# hall_sensor_break_out.net
KiCad netlist of a schematic drawn in EAGLE
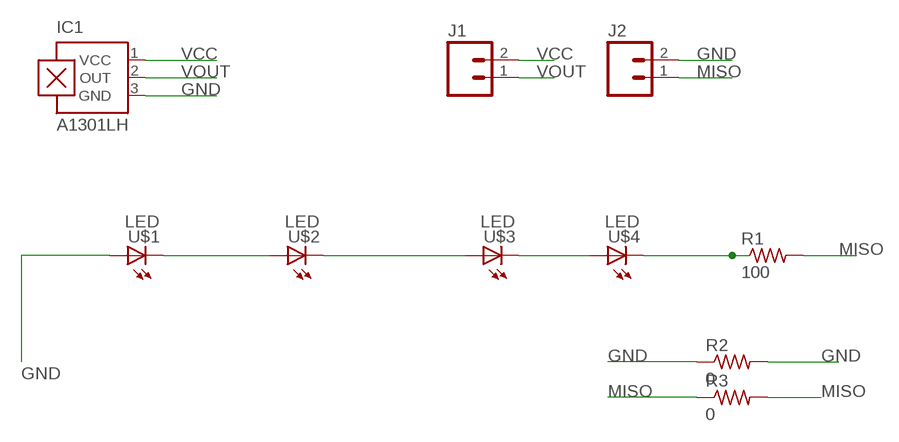
[diagram p0: schematic, sheet 1]

(export (version "E")
  (design (tool "Eeschema 10.0.6"))
  (components
    (comp (ref "IC1")
      (value "A1301LH")
      (footprint "eagle-import:SOT23-W")
      (fields (field (name "MF") "ALLEGRO MICROSYSTEMS, INC.") (field (name "MPN") "A1301ELHLT-T"))
      (libsource (lib "eagle-import") (part "A13?LH01"))
    )
    (comp (ref "J1")
      (value "M02POLAR_LOCK")
      (footprint "eagle-import:MOLEX-1X2_LOCK")
      (libsource (lib "eagle-import") (part "M02POLAR_LOCK"))
    )
    (comp (ref "J2")
      (value "M02POLAR_LOCK")
      (footprint "eagle-import:MOLEX-1X2_LOCK")
      (libsource (lib "eagle-import") (part "M02POLAR_LOCK"))
    )
    (comp (ref "R1")
      (value "100")
      (footprint "eagle-import:R1206FAB")
      (libsource (lib "eagle-import") (part "RES-US1206FAB"))
    )
    (comp (ref "R2")
      (value "0")
      (footprint "eagle-import:R1206FAB")
      (libsource (lib "eagle-import") (part "RES-US1206FAB"))
    )
    (comp (ref "R3")
      (value "0")
      (footprint "eagle-import:R1206FAB")
      (libsource (lib "eagle-import") (part "RES-US1206FAB"))
    )
    (comp (ref "U$1")
      (value "LED")
      (footprint "eagle-import:LED1206")
      (libsource (lib "eagle-import") (part "LED"))
    )
    (comp (ref "U$2")
      (value "LED")
      (footprint "eagle-import:LED1206")
      (libsource (lib "eagle-import") (part "LED"))
    )
    (comp (ref "U$3")
      (value "LED")
      (footprint "eagle-import:LED1206")
      (libsource (lib "eagle-import") (part "LED"))
    )
    (comp (ref "U$4")
      (value "LED")
      (footprint "eagle-import:LED1206")
      (libsource (lib "eagle-import") (part "LED"))
    )
  )
  (nets
    (net (code "1") (name "/GND") (class "Default")
      (node (ref "IC1") (pin "3") (pinfunction "GND_3") (pintype "power_in"))
      (node (ref "J2") (pin "2") (pinfunction "2_2") (pintype "passive"))
      (node (ref "R2") (pin "1") (pinfunction "1_1") (pintype "passive"))
      (node (ref "R2") (pin "2") (pinfunction "2_2") (pintype "passive"))
      (node (ref "U$1") (pin "1") (pinfunction "A_1") (pintype "passive"))
    )
    (net (code "2") (name "/MISO") (class "Default")
      (node (ref "J2") (pin "1") (pinfunction "1_1") (pintype "passive"))
      (node (ref "R1") (pin "2") (pinfunction "2_2") (pintype "passive"))
      (node (ref "R3") (pin "1") (pinfunction "1_1") (pintype "passive"))
      (node (ref "R3") (pin "2") (pinfunction "2_2") (pintype "passive"))
    )
    (net (code "3") (name "/VCC") (class "Default")
      (node (ref "IC1") (pin "1") (pinfunction "VCC_1") (pintype "power_in"))
      (node (ref "J1") (pin "2") (pinfunction "2_2") (pintype "passive"))
    )
    (net (code "4") (name "/VOUT") (class "Default")
      (node (ref "IC1") (pin "2") (pinfunction "OUT_2") (pintype "output"))
      (node (ref "J1") (pin "1") (pinfunction "1_1") (pintype "passive"))
    )
    (net (code "5") (name "Net-(U$1-C)") (class "Default")
      (node (ref "U$1") (pin "2") (pinfunction "C_2") (pintype "passive"))
      (node (ref "U$2") (pin "1") (pinfunction "A_1") (pintype "passive"))
    )
    (net (code "6") (name "Net-(U$2-C)") (class "Default")
      (node (ref "U$2") (pin "2") (pinfunction "C_2") (pintype "passive"))
      (node (ref "U$3") (pin "1") (pinfunction "A_1") (pintype "passive"))
    )
    (net (code "7") (name "Net-(U$3-C)") (class "Default")
      (node (ref "U$3") (pin "2") (pinfunction "C_2") (pintype "passive"))
      (node (ref "U$4") (pin "1") (pinfunction "A_1") (pintype "passive"))
    )
    (net (code "8") (name "Net-(U$4-C)") (class "Default")
      (node (ref "R1") (pin "1") (pinfunction "1_1") (pintype "passive"))
      (node (ref "U$4") (pin "2") (pinfunction "C_2") (pintype "passive"))
    )
  )
)
